# TSAL.net
KiCad netlist of a schematic drawn in EAGLE
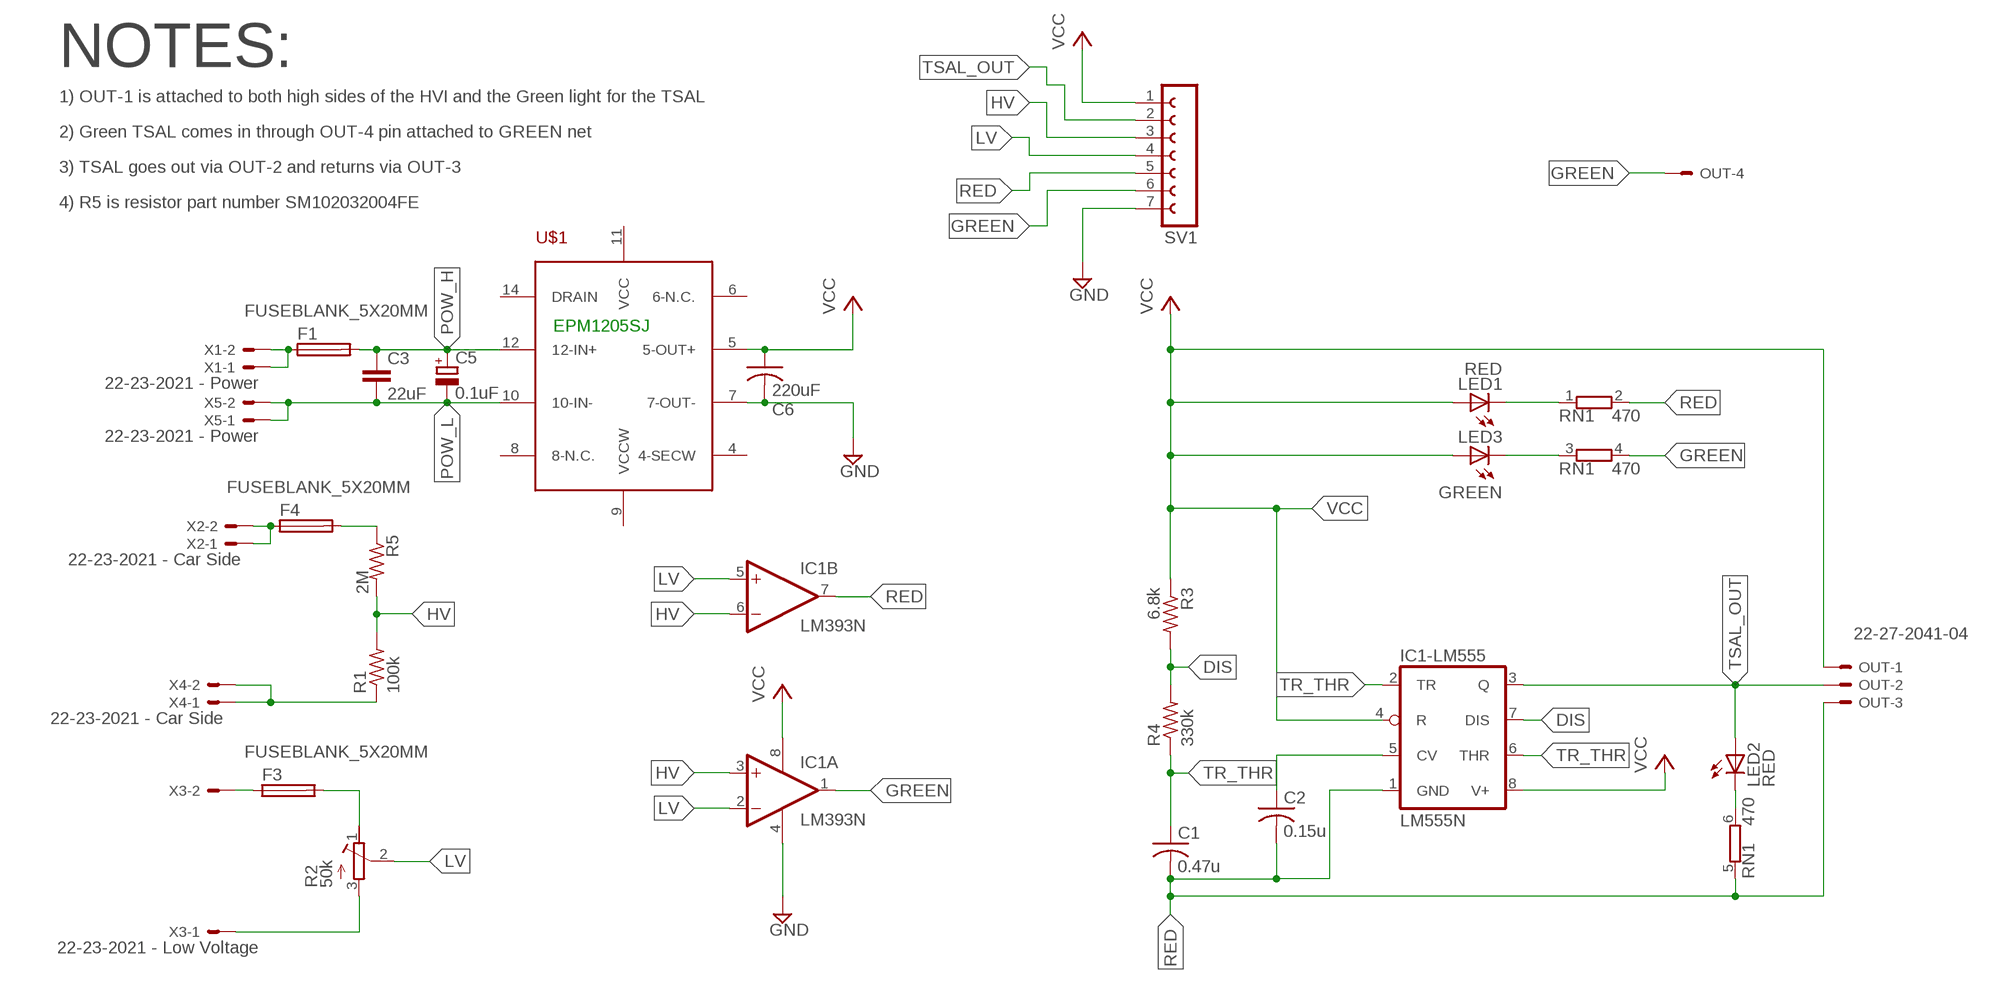
[diagram p0: schematic, sheet 1]

(export (version "E")
  (design (tool "Eeschema 10.0.6"))
  (components
    (comp (ref "C1")
      (value "0.47u")
      (footprint "eagle-import:C050-075X075")
      (libsource (lib "eagle-import") (part "C-US050-075X075"))
    )
    (comp (ref "C2")
      (value "0.15u")
      (footprint "eagle-import:C050-075X075")
      (libsource (lib "eagle-import") (part "C-US050-075X075"))
    )
    (comp (ref "C3")
      (value "22uF")
      (footprint "eagle-import:C150-091X182")
      (libsource (lib "eagle-import") (part "C-EU150-091X182"))
    )
    (comp (ref "C5")
      (value "0.1uF")
      (footprint "eagle-import:E7,5-16")
      (libsource (lib "eagle-import") (part "CPOL-EUE7.5-16"))
    )
    (comp (ref "C6")
      (value "220uF")
      (footprint "eagle-import:C050-055X075")
      (libsource (lib "eagle-import") (part "C-US050-055X075"))
    )
    (comp (ref "F1")
      (value "FUSEBLANK_5X20MM")
      (footprint "eagle-import:FUSE_HOLDER_5X20MM")
      (libsource (lib "eagle-import") (part "FUSEBLANK_5X20MM"))
    )
    (comp (ref "F3")
      (value "FUSEBLANK_5X20MM")
      (footprint "eagle-import:FUSE_HOLDER_5X20MM")
      (libsource (lib "eagle-import") (part "FUSEBLANK_5X20MM"))
    )
    (comp (ref "F4")
      (value "FUSEBLANK_5X20MM")
      (footprint "eagle-import:FUSE_HOLDER_5X20MM")
      (libsource (lib "eagle-import") (part "FUSEBLANK_5X20MM"))
    )
    (comp (ref "IC1")
      (value "LM393N")
      (footprint "eagle-import:DIL08")
      (libsource (lib "eagle-import") (part "LM393N"))
    )
    (comp (ref "IC1-LM555")
      (value "LM555N")
      (footprint "eagle-import:DIL08")
      (libsource (lib "eagle-import") (part "555NLM"))
    )
    (comp (ref "LED1")
      (value "RED")
      (footprint "eagle-import:LED3MM")
      (libsource (lib "eagle-import") (part "LED3MM"))
    )
    (comp (ref "LED2")
      (value "RED")
      (footprint "eagle-import:LED3MM")
      (libsource (lib "eagle-import") (part "LED3MM"))
    )
    (comp (ref "LED3")
      (value "GREEN")
      (footprint "eagle-import:LED3MM")
      (libsource (lib "eagle-import") (part "LED3MM"))
    )
    (comp (ref "OUT")
      (value "22-27-2041-04")
      (footprint "eagle-import:6410-04")
      (fields (field (name "MF") "MOLEX"))
      (libsource (lib "eagle-import") (part "22-?-0427-2041"))
    )
    (comp (ref "R1")
      (value "100k")
      (footprint "eagle-import:0207_10")
      (libsource (lib "eagle-import") (part "R-US_0207/10"))
    )
    (comp (ref "R2")
      (value "50k")
      (footprint "eagle-import:RTRIM3006P")
      (libsource (lib "eagle-import") (part "R-TRIMM3006P"))
    )
    (comp (ref "R3")
      (value "6.8k")
      (footprint "eagle-import:0309_12")
      (libsource (lib "eagle-import") (part "R-US_0309/12"))
    )
    (comp (ref "R4")
      (value "330k")
      (footprint "eagle-import:0309_12")
      (libsource (lib "eagle-import") (part "R-US_0309/12"))
    )
    (comp (ref "R5")
      (value "2M")
      (footprint "eagle-import:0207_10")
      (libsource (lib "eagle-import") (part "R-US_0207/10"))
    )
    (comp (ref "RN1")
      (value "470")
      (footprint "eagle-import:SIL6")
      (libsource (lib "eagle-import") (part "E3RP"))
    )
    (comp (ref "SV1")
      (value "FE07W")
      (footprint "eagle-import:FE07W")
      (libsource (lib "eagle-import") (part "FE07W"))
    )
    (comp (ref "U$1")
      (value "EPM1205SJ")
      (footprint "eagle-import:EPM1205SJ")
      (libsource (lib "eagle-import") (part "EPM1205SJ"))
    )
    (comp (ref "X1")
      (value "22-23-2021 - Power")
      (footprint "eagle-import:22-23-2021")
      (fields (field (name "MF") "MOLEX") (field (name "MPN") "22-23-2021"))
      (libsource (lib "eagle-import") (part "22-23-2021"))
    )
    (comp (ref "X2")
      (value "22-23-2021 - Car Side")
      (footprint "eagle-import:22-23-2021")
      (fields (field (name "MF") "MOLEX") (field (name "MPN") "22-23-2021"))
      (libsource (lib "eagle-import") (part "22-23-2021"))
    )
    (comp (ref "X3")
      (value "22-23-2021 - Low Voltage")
      (footprint "eagle-import:22-23-2021")
      (fields (field (name "MF") "MOLEX") (field (name "MPN") "22-23-2021"))
      (libsource (lib "eagle-import") (part "22-23-2021"))
    )
    (comp (ref "X4")
      (value "22-23-2021 - Car Side")
      (footprint "eagle-import:22-23-2021")
      (fields (field (name "MF") "MOLEX") (field (name "MPN") "22-23-2021"))
      (libsource (lib "eagle-import") (part "22-23-2021"))
    )
    (comp (ref "X5")
      (value "22-23-2021 - Power")
      (footprint "eagle-import:22-23-2021")
      (fields (field (name "MF") "MOLEX") (field (name "MPN") "22-23-2021"))
      (libsource (lib "eagle-import") (part "22-23-2021"))
    )
  )
  (nets
    (net (code "1") (name "DIS") (class "Default")
      (node (ref "IC1-LM555") (pin "7") (pinfunction "DIS_7") (pintype "input"))
      (node (ref "R3") (pin "2") (pinfunction "2_2") (pintype "passive"))
      (node (ref "R4") (pin "2") (pinfunction "2_2") (pintype "passive"))
    )
    (net (code "2") (name "GND") (class "Default")
      (node (ref "C6") (pin "2") (pinfunction "2_2") (pintype "passive"))
      (node (ref "IC1") (pin "4") (pinfunction "V-_4") (pintype "power_in"))
      (node (ref "SV1") (pin "7") (pinfunction "7_7") (pintype "passive"))
      (node (ref "U$1") (pin "7") (pinfunction "7-OUT-_7") (pintype "bidirectional"))
    )
    (net (code "3") (name "GREEN") (class "Default")
      (node (ref "IC1") (pin "1") (pinfunction "OUT_1") (pintype "output"))
      (node (ref "OUT") (pin "4") (pinfunction "S_4") (pintype "passive"))
      (node (ref "RN1") (pin "4") (pinfunction "2_4") (pintype "passive"))
      (node (ref "SV1") (pin "6") (pinfunction "6_6") (pintype "passive"))
    )
    (net (code "4") (name "HV") (class "Default")
      (node (ref "IC1") (pin "3") (pinfunction "+IN_3") (pintype "input"))
      (node (ref "IC1") (pin "6") (pinfunction "-IN_6") (pintype "input"))
      (node (ref "R1") (pin "2") (pinfunction "2_2") (pintype "passive"))
      (node (ref "R5") (pin "2") (pinfunction "2_2") (pintype "passive"))
      (node (ref "SV1") (pin "3") (pinfunction "3_3") (pintype "passive"))
    )
    (net (code "5") (name "LV") (class "Default")
      (node (ref "IC1") (pin "2") (pinfunction "-IN_2") (pintype "input"))
      (node (ref "IC1") (pin "5") (pinfunction "+IN_5") (pintype "input"))
      (node (ref "R2") (pin "2") (pinfunction "S_2") (pintype "passive"))
      (node (ref "SV1") (pin "4") (pinfunction "4_4") (pintype "passive"))
    )
    (net (code "6") (name "Net-(F4-Pad2)") (class "Default")
      (node (ref "F4") (pin "2") (pinfunction "2_2") (pintype "passive"))
      (node (ref "R5") (pin "1") (pinfunction "1_1") (pintype "passive"))
    )
    (net (code "7") (name "Net-(IC1-LM555-CV)") (class "Default")
      (node (ref "C2") (pin "1") (pinfunction "1_1") (pintype "passive"))
      (node (ref "IC1-LM555") (pin "5") (pinfunction "CV_5") (pintype "input"))
    )
    (net (code "8") (name "Net-(LED1-C)") (class "Default")
      (node (ref "LED1") (pin "K") (pinfunction "C_K") (pintype "passive"))
      (node (ref "RN1") (pin "1") (pinfunction "1_1") (pintype "passive"))
    )
    (net (code "9") (name "Net-(LED2-C)") (class "Default")
      (node (ref "LED2") (pin "K") (pinfunction "C_K") (pintype "passive"))
      (node (ref "RN1") (pin "6") (pinfunction "2_6") (pintype "passive"))
    )
    (net (code "10") (name "Net-(LED3-C)") (class "Default")
      (node (ref "LED3") (pin "K") (pinfunction "C_K") (pintype "passive"))
      (node (ref "RN1") (pin "3") (pinfunction "1_3") (pintype "passive"))
    )
    (net (code "11") (name "Net-(R2-A)") (class "Default")
      (node (ref "R2") (pin "3") (pinfunction "A_3") (pintype "passive"))
      (node (ref "X3") (pin "1") (pinfunction "S_1") (pintype "passive"))
    )
    (net (code "12") (name "Net-(R2-E)") (class "Default")
      (node (ref "F3") (pin "2") (pinfunction "2_2") (pintype "passive"))
      (node (ref "R2") (pin "1") (pinfunction "E_1") (pintype "passive"))
    )
    (net (code "13") (name "Net-(X1A-S)") (class "Default")
      (node (ref "F1") (pin "1") (pinfunction "1_1") (pintype "passive"))
      (node (ref "X1") (pin "1") (pinfunction "S_1") (pintype "passive"))
      (node (ref "X1") (pin "2") (pinfunction "S_2") (pintype "passive"))
    )
    (net (code "14") (name "Net-(X2A-S)") (class "Default")
      (node (ref "F4") (pin "1") (pinfunction "1_1") (pintype "passive"))
      (node (ref "X2") (pin "1") (pinfunction "S_1") (pintype "passive"))
      (node (ref "X2") (pin "2") (pinfunction "S_2") (pintype "passive"))
    )
    (net (code "15") (name "Net-(X3B-S)") (class "Default")
      (node (ref "F3") (pin "1") (pinfunction "1_1") (pintype "passive"))
      (node (ref "X3") (pin "2") (pinfunction "S_2") (pintype "passive"))
    )
    (net (code "16") (name "Net-(X4A-S)") (class "Default")
      (node (ref "R1") (pin "1") (pinfunction "1_1") (pintype "passive"))
      (node (ref "X4") (pin "1") (pinfunction "S_1") (pintype "passive"))
      (node (ref "X4") (pin "2") (pinfunction "S_2") (pintype "passive"))
    )
    (net (code "17") (name "POW_H") (class "Default")
      (node (ref "C3") (pin "1") (pinfunction "1_1") (pintype "passive"))
      (node (ref "C5") (pin "+") (pinfunction "+_+") (pintype "passive"))
      (node (ref "F1") (pin "2") (pinfunction "2_2") (pintype "passive"))
      (node (ref "U$1") (pin "12") (pinfunction "12-IN+_12") (pintype "bidirectional"))
    )
    (net (code "18") (name "POW_L") (class "Default")
      (node (ref "C3") (pin "2") (pinfunction "2_2") (pintype "passive"))
      (node (ref "C5") (pin "-") (pinfunction "-_-") (pintype "passive"))
      (node (ref "U$1") (pin "10") (pinfunction "10-IN-_10") (pintype "bidirectional"))
      (node (ref "X5") (pin "1") (pinfunction "S_1") (pintype "passive"))
      (node (ref "X5") (pin "2") (pinfunction "S_2") (pintype "passive"))
    )
    (net (code "19") (name "RED") (class "Default")
      (node (ref "C1") (pin "2") (pinfunction "2_2") (pintype "passive"))
      (node (ref "C2") (pin "2") (pinfunction "2_2") (pintype "passive"))
      (node (ref "IC1") (pin "7") (pinfunction "OUT_7") (pintype "output"))
      (node (ref "IC1-LM555") (pin "1") (pinfunction "GND_1") (pintype "power_in"))
      (node (ref "OUT") (pin "3") (pinfunction "S_3") (pintype "passive"))
      (node (ref "RN1") (pin "2") (pinfunction "2_2") (pintype "passive"))
      (node (ref "RN1") (pin "5") (pinfunction "1_5") (pintype "passive"))
      (node (ref "SV1") (pin "5") (pinfunction "5_5") (pintype "passive"))
    )
    (net (code "20") (name "TR_THR") (class "Default")
      (node (ref "C1") (pin "1") (pinfunction "1_1") (pintype "passive"))
      (node (ref "IC1-LM555") (pin "2") (pinfunction "TR_2") (pintype "input"))
      (node (ref "IC1-LM555") (pin "6") (pinfunction "THR_6") (pintype "input"))
      (node (ref "R4") (pin "1") (pinfunction "1_1") (pintype "passive"))
    )
    (net (code "21") (name "TSAL_OUT") (class "Default")
      (node (ref "IC1-LM555") (pin "3") (pinfunction "Q_3") (pintype "output"))
      (node (ref "LED2") (pin "A") (pinfunction "A_A") (pintype "passive"))
      (node (ref "OUT") (pin "2") (pinfunction "S_2") (pintype "passive"))
      (node (ref "SV1") (pin "2") (pinfunction "2_2") (pintype "passive"))
    )
    (net (code "22") (name "VCC") (class "Default")
      (node (ref "C6") (pin "1") (pinfunction "1_1") (pintype "passive"))
      (node (ref "IC1") (pin "8") (pinfunction "V+_8") (pintype "power_in"))
      (node (ref "IC1-LM555") (pin "4") (pinfunction "R_4") (pintype "input"))
      (node (ref "IC1-LM555") (pin "8") (pinfunction "V+_8") (pintype "power_in"))
      (node (ref "LED1") (pin "A") (pinfunction "A_A") (pintype "passive"))
      (node (ref "LED3") (pin "A") (pinfunction "A_A") (pintype "passive"))
      (node (ref "OUT") (pin "1") (pinfunction "S_1") (pintype "passive"))
      (node (ref "R3") (pin "1") (pinfunction "1_1") (pintype "passive"))
      (node (ref "SV1") (pin "1") (pinfunction "1_1") (pintype "passive"))
      (node (ref "U$1") (pin "5") (pinfunction "5-OUT+_5") (pintype "bidirectional"))
    )
    (net (code "23") (name "unconnected-(U$1-4-SECW-Pad4)") (class "Default")
      (node (ref "U$1") (pin "4") (pinfunction "4-SECW_4") (pintype "bidirectional"))
    )
    (net (code "24") (name "unconnected-(U$1-6-N.C.-Pad6)") (class "Default")
      (node (ref "U$1") (pin "6") (pinfunction "6-N.C._6") (pintype "bidirectional"))
    )
    (net (code "25") (name "unconnected-(U$1-8-N.C.-Pad8)") (class "Default")
      (node (ref "U$1") (pin "8") (pinfunction "8-N.C._8") (pintype "bidirectional"))
    )
    (net (code "26") (name "unconnected-(U$1-DRAIN-Pad14)") (class "Default")
      (node (ref "U$1") (pin "14") (pinfunction "DRAIN_14") (pintype "bidirectional"))
    )
    (net (code "27") (name "unconnected-(U$1-VCC-Pad11)") (class "Default")
      (node (ref "U$1") (pin "11") (pinfunction "VCC_11") (pintype "bidirectional"))
    )
    (net (code "28") (name "unconnected-(U$1-VCCW-Pad9)") (class "Default")
      (node (ref "U$1") (pin "9") (pinfunction "VCCW_9") (pintype "bidirectional"))
    )
  )
)
